# LB_BIT_i25_mp3Player-v03_3_3_OHW.net
KiCad netlist of a schematic drawn in EAGLE
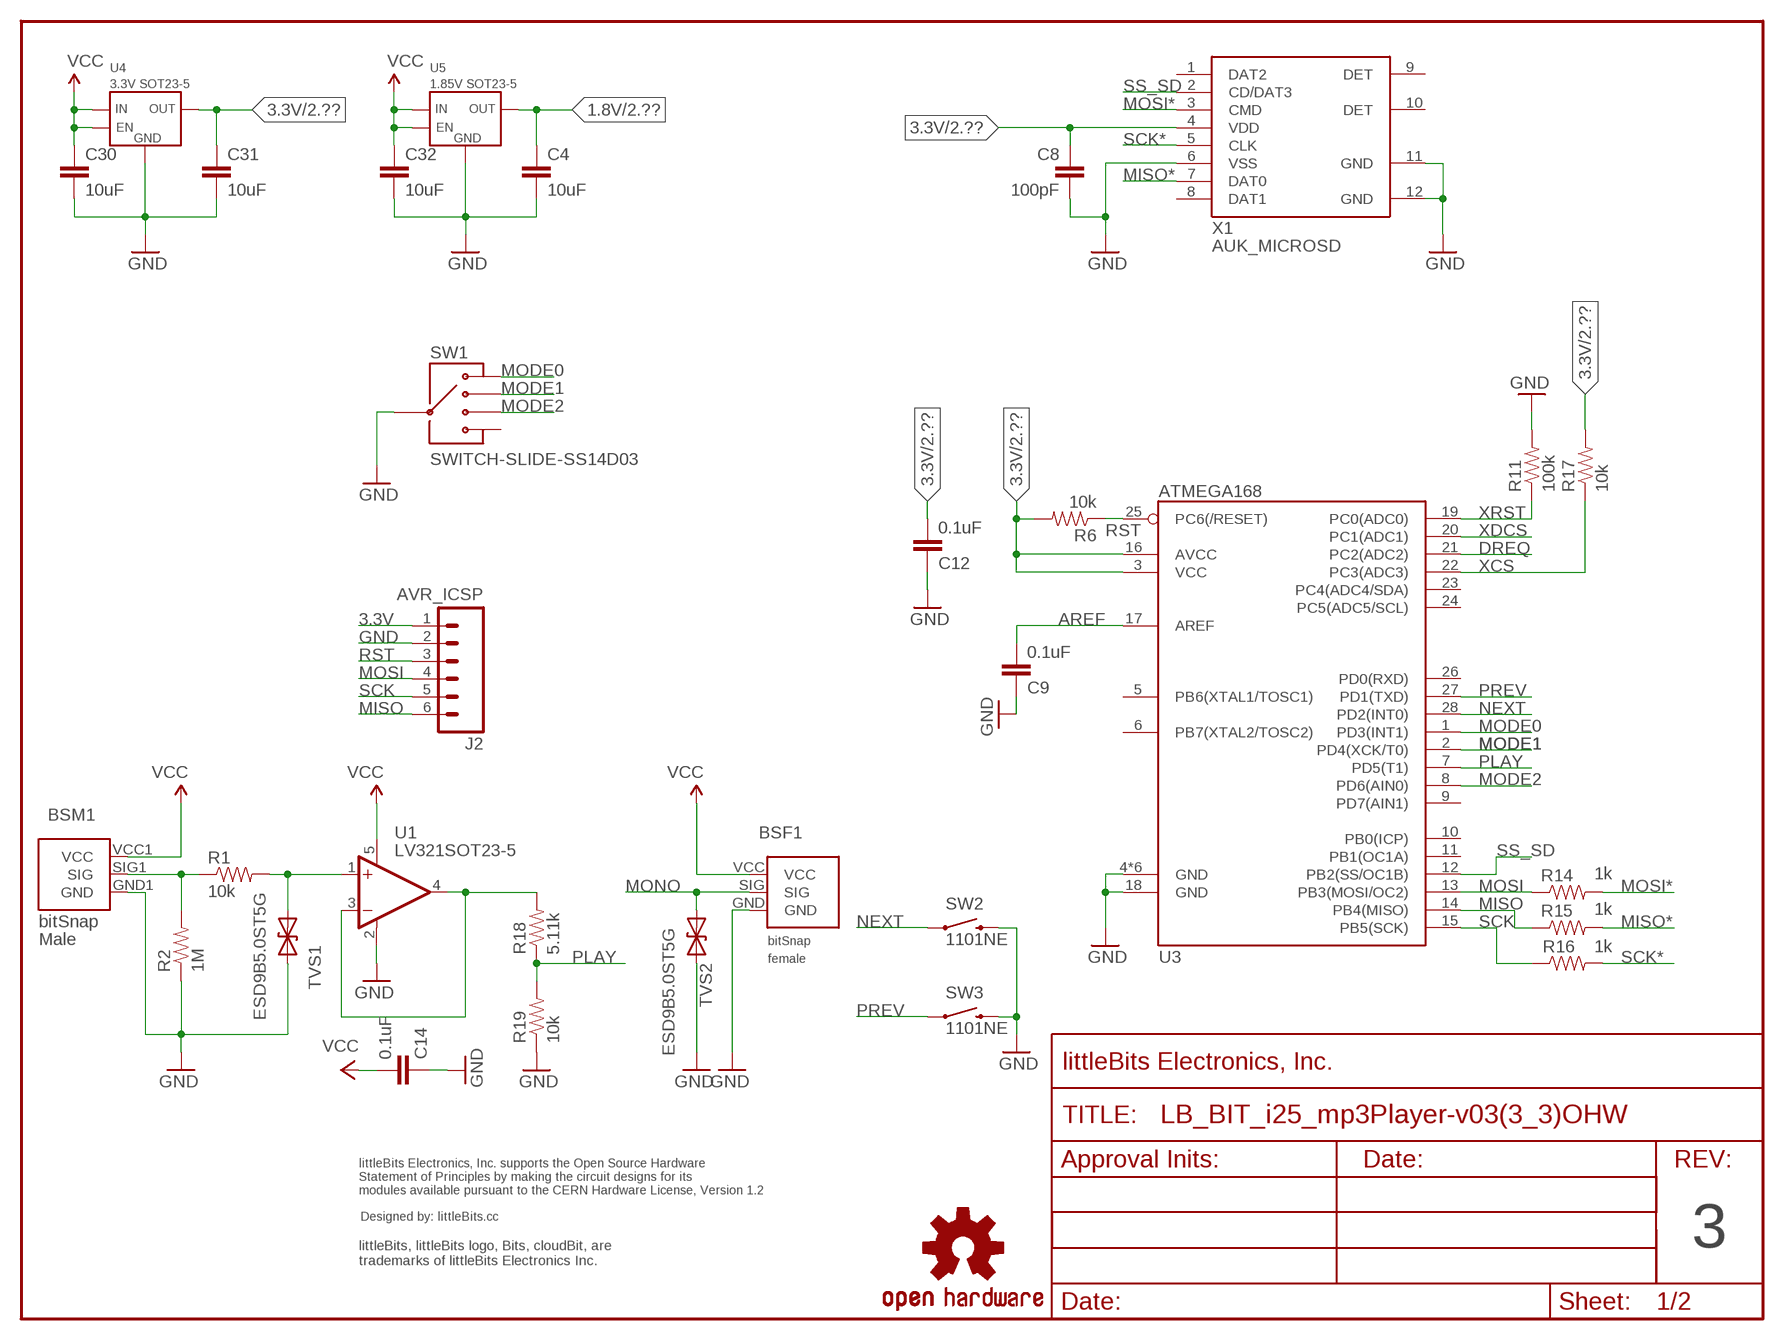
[diagram p0: schematic, sheet 1]
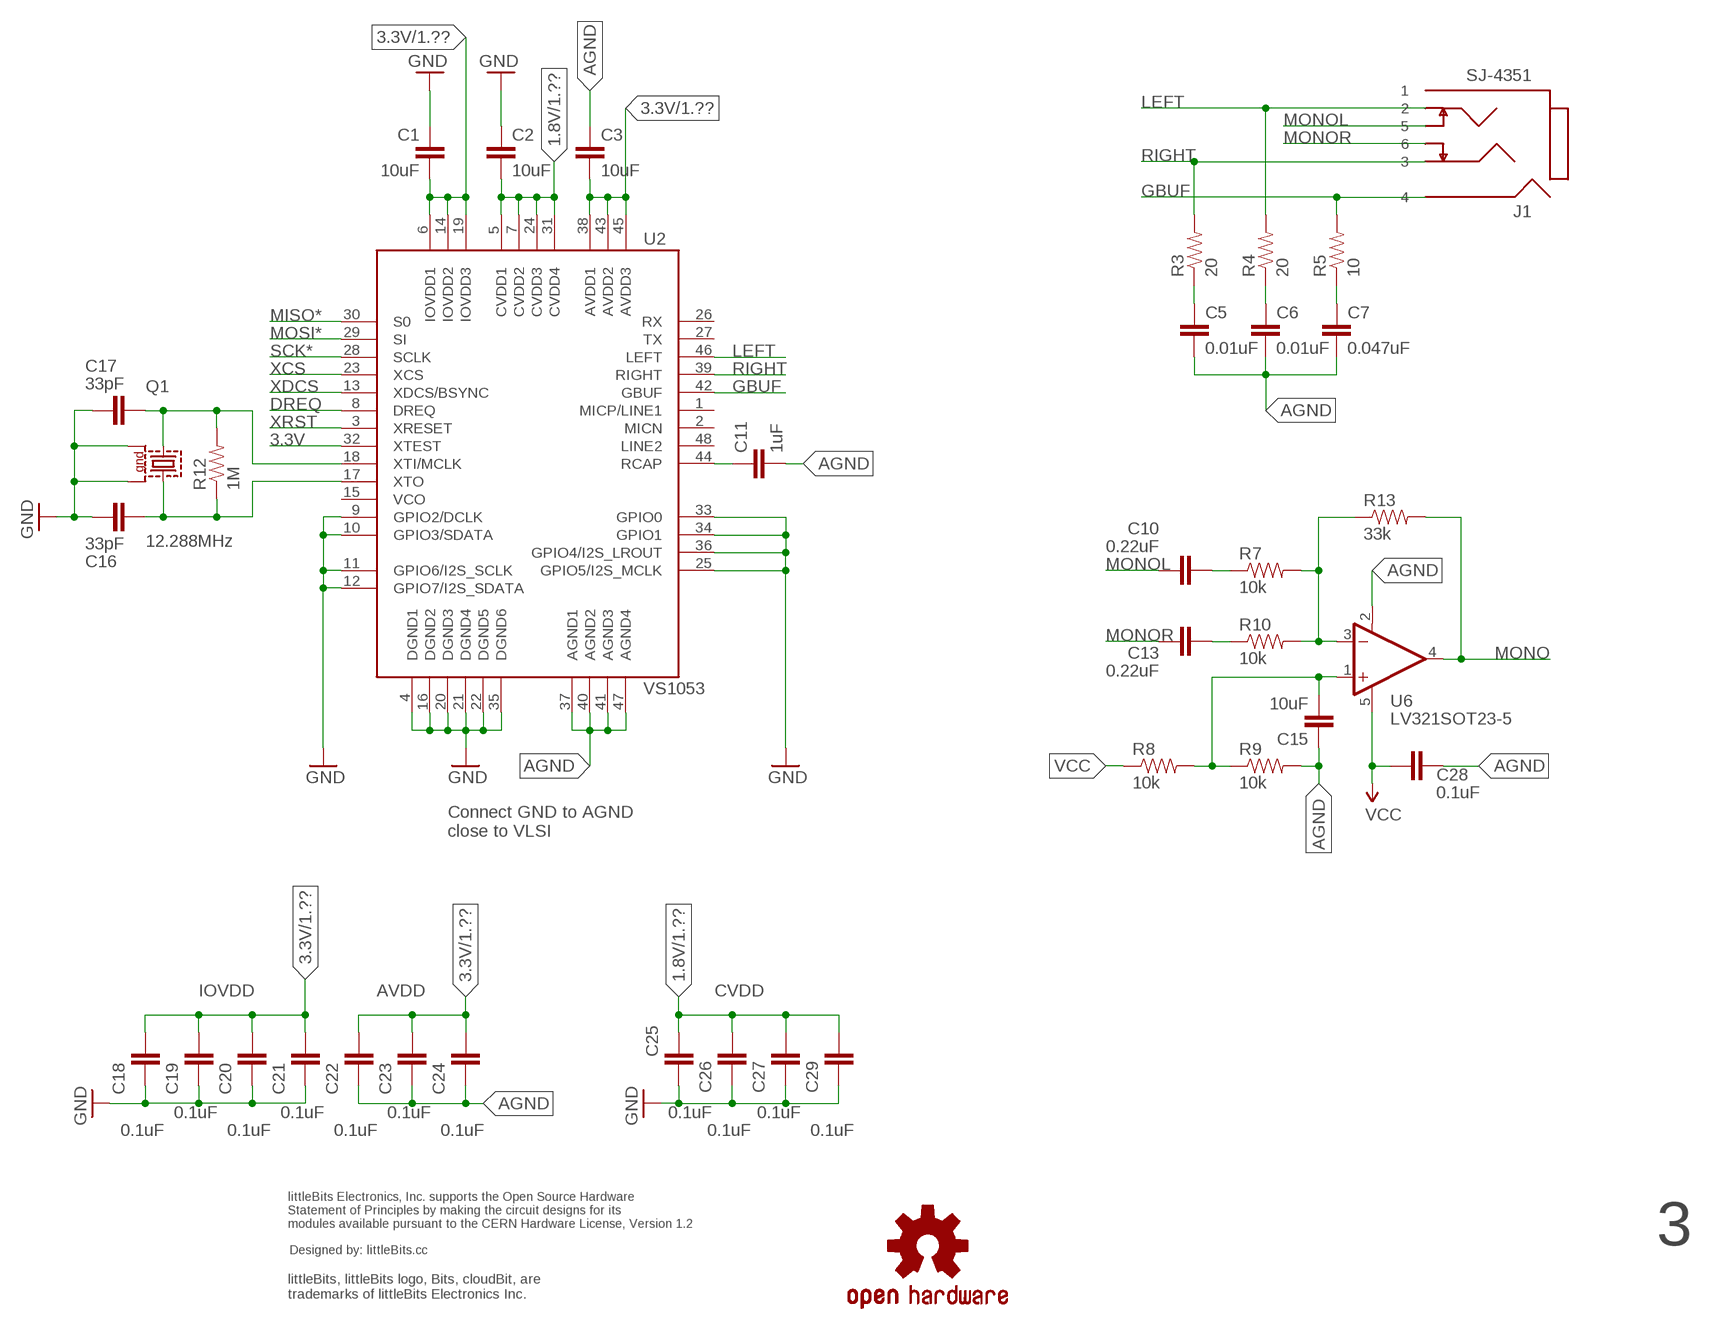
[diagram p1: schematic, sheet 2]

(export (version "E")
  (design (tool "Eeschema 10.0.6"))
  (components
    (comp (ref "BSF1")
      (value "BITSNAP_V03_FEMALE")
      (footprint "eagle-import:BITSNAP_V03_FEMALE")
      (libsource (lib "eagle-import") (part "BITSNAP_V03_FEMALE"))
    )
    (comp (ref "BSM1")
      (value "BITSNAP_V03_MALE")
      (footprint "eagle-import:BITSNAP_V03_MALE")
      (libsource (lib "eagle-import") (part "BITSNAP_V03_MALE"))
    )
    (comp (ref "C4")
      (value "10uF")
      (footprint "eagle-import:CAP-0603")
      (libsource (lib "eagle-import") (part "CAPCAP-0603"))
    )
    (comp (ref "C8")
      (value "100pF")
      (footprint "eagle-import:CAP-0603")
      (libsource (lib "eagle-import") (part "CAPCAP-0603"))
    )
    (comp (ref "C9")
      (value "0.1uF")
      (footprint "eagle-import:CAP-0402")
      (libsource (lib "eagle-import") (part "CAPCAP-0402"))
    )
    (comp (ref "C12")
      (value "0.1uF")
      (footprint "eagle-import:CAP-0402")
      (libsource (lib "eagle-import") (part "CAPCAP-0402"))
    )
    (comp (ref "C14")
      (value "0.1uF")
      (footprint "eagle-import:CAP-0603")
      (libsource (lib "eagle-import") (part "CAPCAP-0603"))
    )
    (comp (ref "C30")
      (value "10uF")
      (footprint "eagle-import:CAP-0603")
      (libsource (lib "eagle-import") (part "CAPCAP-0603"))
    )
    (comp (ref "C31")
      (value "10uF")
      (footprint "eagle-import:CAP-0603")
      (libsource (lib "eagle-import") (part "CAPCAP-0603"))
    )
    (comp (ref "C32")
      (value "10uF")
      (footprint "eagle-import:CAP-0603")
      (libsource (lib "eagle-import") (part "CAPCAP-0603"))
    )
    (comp (ref "J2")
      (value "AVR_ICSP")
      (footprint "eagle-import:SIP6-SM-0.1IN-NOS.S-MIN")
      (libsource (lib "eagle-import") (part "HRD-60.1INCH_NO_SILKSCREEN_SMALL"))
    )
    (comp (ref "R1")
      (value "10k")
      (footprint "eagle-import:RES-0603")
      (libsource (lib "eagle-import") (part "RESISTOR0603"))
    )
    (comp (ref "R2")
      (value "1M")
      (footprint "eagle-import:RES-0603")
      (libsource (lib "eagle-import") (part "RESISTOR0603"))
    )
    (comp (ref "R6")
      (value "10k")
      (footprint "eagle-import:RES-0603")
      (libsource (lib "eagle-import") (part "RESISTOR0603"))
    )
    (comp (ref "R11")
      (value "100k")
      (footprint "eagle-import:RES-0603")
      (libsource (lib "eagle-import") (part "RESISTOR0603"))
    )
    (comp (ref "R14")
      (value "1k")
      (footprint "eagle-import:RES-0603")
      (libsource (lib "eagle-import") (part "RESISTOR0603"))
    )
    (comp (ref "R15")
      (value "1k")
      (footprint "eagle-import:RES-0603")
      (libsource (lib "eagle-import") (part "RESISTOR0603"))
    )
    (comp (ref "R16")
      (value "1k")
      (footprint "eagle-import:RES-0603")
      (libsource (lib "eagle-import") (part "RESISTOR0603"))
    )
    (comp (ref "R17")
      (value "10k")
      (footprint "eagle-import:RES-0603")
      (libsource (lib "eagle-import") (part "RESISTOR0603"))
    )
    (comp (ref "R18")
      (value "5.11k")
      (footprint "eagle-import:RES-0603")
      (libsource (lib "eagle-import") (part "RESISTOR0603"))
    )
    (comp (ref "R19")
      (value "10k")
      (footprint "eagle-import:RES-0603")
      (libsource (lib "eagle-import") (part "RESISTOR0603"))
    )
    (comp (ref "SW1")
      (value "SWITCH-SLIDE-SS14D03")
      (footprint "eagle-import:SWITCH-SLIDE-SP4T-SS14D03")
      (fields (field (name "MFG") "Vimex") (field (name "MPN") "SS-14D03"))
      (libsource (lib "eagle-import") (part "SWITCH-SLIDE-SS14D03"))
    )
    (comp (ref "SW2")
      (value "1101NE")
      (footprint "eagle-import:TACTILE-SWITCH-1101NE")
      (libsource (lib "eagle-import") (part "SWITCH-MOMENTARY-2-SMD-1101NE"))
    )
    (comp (ref "SW3")
      (value "1101NE")
      (footprint "eagle-import:TACTILE-SWITCH-1101NE")
      (libsource (lib "eagle-import") (part "SWITCH-MOMENTARY-2-SMD-1101NE"))
    )
    (comp (ref "TVS1")
      (value "ESD9B5.0ST5G")
      (footprint "eagle-import:SOD-923")
      (libsource (lib "eagle-import") (part "DIODE-TVSSOD-923"))
    )
    (comp (ref "TVS2")
      (value "ESD9B5.0ST5G")
      (footprint "eagle-import:SOD-923")
      (libsource (lib "eagle-import") (part "DIODE-TVSSOD-923"))
    )
    (comp (ref "U$1")
      (value "OSHWCREDIT")
      (footprint "eagle-import:OSHWCREDIT")
      (libsource (lib "eagle-import") (part "OSHWCREDIT"))
    )
    (comp (ref "U$2")
      (value "OSHW-LOGOL")
      (footprint "eagle-import:OSHW-LOGO-L")
      (libsource (lib "eagle-import") (part "OSHW-LOGOL"))
    )
    (comp (ref "U$38")
      (value "FRAME-LETTER-OHWOHW")
      (footprint "eagle-import:FABDWG01-OHW")
      (libsource (lib "eagle-import") (part "FRAME-LETTER-OHWOHW"))
    )
    (comp (ref "U1")
      (value "LV321SOT23-5")
      (footprint "eagle-import:SOT23-5")
      (libsource (lib "eagle-import") (part "LV321SOT23-5"))
    )
    (comp (ref "U3")
      (value "ATMEGA168")
      (footprint "eagle-import:VQFN28")
      (libsource (lib "eagle-import") (part "ATMEGA168-28PINVFQFN-28"))
    )
    (comp (ref "U4")
      (value "3.3V SOT23-5")
      (footprint "eagle-import:SOT23-5")
      (libsource (lib "eagle-import") (part "V_REG_SOT23-5_EN"))
    )
    (comp (ref "U5")
      (value "1.85V SOT23-5")
      (footprint "eagle-import:SOT23-5")
      (libsource (lib "eagle-import") (part "V_REG_SOT23-5_EN"))
    )
    (comp (ref "X1")
      (value "AUK_MICROSD")
      (footprint "eagle-import:AUK_TFC08WP01-R1K-H")
      (libsource (lib "eagle-import") (part "AUK_MICROSD"))
    )
    (comp (ref "C1")
      (value "10uF")
      (footprint "eagle-import:CAP-0603")
      (libsource (lib "eagle-import") (part "CAPCAP-0603"))
    )
    (comp (ref "C2")
      (value "10uF")
      (footprint "eagle-import:CAP-0603")
      (libsource (lib "eagle-import") (part "CAPCAP-0603"))
    )
    (comp (ref "C3")
      (value "10uF")
      (footprint "eagle-import:CAP-0603")
      (libsource (lib "eagle-import") (part "CAPCAP-0603"))
    )
    (comp (ref "C5")
      (value "0.01uF")
      (footprint "eagle-import:CAP-0603")
      (libsource (lib "eagle-import") (part "CAPCAP-0603"))
    )
    (comp (ref "C6")
      (value "0.01uF")
      (footprint "eagle-import:CAP-0603")
      (libsource (lib "eagle-import") (part "CAPCAP-0603"))
    )
    (comp (ref "C7")
      (value "0.047uF")
      (footprint "eagle-import:CAP-0603")
      (libsource (lib "eagle-import") (part "CAPCAP-0603"))
    )
    (comp (ref "C10")
      (value "0.22uF")
      (footprint "eagle-import:CAP-0603")
      (libsource (lib "eagle-import") (part "CAPCAP-0603"))
    )
    (comp (ref "C11")
      (value "1uF")
      (footprint "eagle-import:CAP-0402")
      (libsource (lib "eagle-import") (part "CAPCAP-0402"))
    )
    (comp (ref "C13")
      (value "0.22uF")
      (footprint "eagle-import:CAP-0603")
      (libsource (lib "eagle-import") (part "CAPCAP-0603"))
    )
    (comp (ref "C15")
      (value "10uF")
      (footprint "eagle-import:CAP-0603")
      (libsource (lib "eagle-import") (part "CAPCAP-0603"))
    )
    (comp (ref "C16")
      (value "33pF")
      (footprint "eagle-import:CAP-0603")
      (libsource (lib "eagle-import") (part "CAPCAP-0603"))
    )
    (comp (ref "C17")
      (value "33pF")
      (footprint "eagle-import:CAP-0603")
      (libsource (lib "eagle-import") (part "CAPCAP-0603"))
    )
    (comp (ref "C18")
      (value "0.1uF")
      (footprint "eagle-import:CAP-0402")
      (libsource (lib "eagle-import") (part "CAPCAP-0402"))
    )
    (comp (ref "C19")
      (value "0.1uF")
      (footprint "eagle-import:CAP-0402")
      (libsource (lib "eagle-import") (part "CAPCAP-0402"))
    )
    (comp (ref "C20")
      (value "0.1uF")
      (footprint "eagle-import:CAP-0402")
      (libsource (lib "eagle-import") (part "CAPCAP-0402"))
    )
    (comp (ref "C21")
      (value "0.1uF")
      (footprint "eagle-import:CAP-0402")
      (libsource (lib "eagle-import") (part "CAPCAP-0402"))
    )
    (comp (ref "C22")
      (value "0.1uF")
      (footprint "eagle-import:CAP-0402")
      (libsource (lib "eagle-import") (part "CAPCAP-0402"))
    )
    (comp (ref "C23")
      (value "0.1uF")
      (footprint "eagle-import:CAP-0402")
      (libsource (lib "eagle-import") (part "CAPCAP-0402"))
    )
    (comp (ref "C24")
      (value "0.1uF")
      (footprint "eagle-import:CAP-0402")
      (libsource (lib "eagle-import") (part "CAPCAP-0402"))
    )
    (comp (ref "C25")
      (value "0.1uF")
      (footprint "eagle-import:CAP-0402")
      (libsource (lib "eagle-import") (part "CAPCAP-0402"))
    )
    (comp (ref "C26")
      (value "0.1uF")
      (footprint "eagle-import:CAP-0402")
      (libsource (lib "eagle-import") (part "CAPCAP-0402"))
    )
    (comp (ref "C27")
      (value "0.1uF")
      (footprint "eagle-import:CAP-0402")
      (libsource (lib "eagle-import") (part "CAPCAP-0402"))
    )
    (comp (ref "C28")
      (value "0.1uF")
      (footprint "eagle-import:CAP-0603")
      (libsource (lib "eagle-import") (part "CAPCAP-0603"))
    )
    (comp (ref "C29")
      (value "0.1uF")
      (footprint "eagle-import:CAP-0402")
      (libsource (lib "eagle-import") (part "CAPCAP-0402"))
    )
    (comp (ref "J1")
      (value "SJ-4351")
      (footprint "eagle-import:CUI-SJ-4351")
      (libsource (lib "eagle-import") (part "JACK-PHONO-4COND-SW"))
    )
    (comp (ref "Q1")
      (value "12.288MHz")
      (footprint "eagle-import:CRYSTAL-SMD-7B-SERIES-5X3.2MM")
      (fields (field (name "MFG") "TXC") (field (name "MPN") "7B SERIES"))
      (libsource (lib "eagle-import") (part "CRYSTAL-SMD-7B-SERIES-TXC"))
    )
    (comp (ref "R3")
      (value "20")
      (footprint "eagle-import:RES-0603")
      (libsource (lib "eagle-import") (part "RESISTOR0603"))
    )
    (comp (ref "R4")
      (value "20")
      (footprint "eagle-import:RES-0603")
      (libsource (lib "eagle-import") (part "RESISTOR0603"))
    )
    (comp (ref "R5")
      (value "10")
      (footprint "eagle-import:RES-0603")
      (libsource (lib "eagle-import") (part "RESISTOR0603"))
    )
    (comp (ref "R7")
      (value "10k")
      (footprint "eagle-import:RES-0603")
      (libsource (lib "eagle-import") (part "RESISTOR0603"))
    )
    (comp (ref "R8")
      (value "10k")
      (footprint "eagle-import:RES-0603")
      (libsource (lib "eagle-import") (part "RESISTOR0603"))
    )
    (comp (ref "R9")
      (value "10k")
      (footprint "eagle-import:RES-0603")
      (libsource (lib "eagle-import") (part "RESISTOR0603"))
    )
    (comp (ref "R10")
      (value "10k")
      (footprint "eagle-import:RES-0603")
      (libsource (lib "eagle-import") (part "RESISTOR0603"))
    )
    (comp (ref "R12")
      (value "1M")
      (footprint "eagle-import:RES-0603")
      (libsource (lib "eagle-import") (part "RESISTOR0603"))
    )
    (comp (ref "R13")
      (value "33k")
      (footprint "eagle-import:RES-0603")
      (libsource (lib "eagle-import") (part "RESISTOR0603"))
    )
    (comp (ref "U$32")
      (value "OSHWCREDIT")
      (footprint "eagle-import:OSHWCREDIT")
      (libsource (lib "eagle-import") (part "OSHWCREDIT"))
    )
    (comp (ref "U$33")
      (value "OSHW-LOGOL")
      (footprint "eagle-import:OSHW-LOGO-L")
      (libsource (lib "eagle-import") (part "OSHW-LOGOL"))
    )
    (comp (ref "U2")
      (value "VS1053")
      (footprint "eagle-import:LQFP-48")
      (libsource (lib "eagle-import") (part "VS1053"))
    )
    (comp (ref "U6")
      (value "LV321SOT23-5")
      (footprint "eagle-import:SOT23-5")
      (libsource (lib "eagle-import") (part "LV321SOT23-5"))
    )
  )
  (nets
    (net (code "1") (name "1.8V") (class "Default")
      (node (ref "C2") (pin "2") (pinfunction "2_2") (pintype "passive"))
      (node (ref "C25") (pin "1") (pinfunction "1_1") (pintype "passive"))
      (node (ref "C26") (pin "1") (pinfunction "1_1") (pintype "passive"))
      (node (ref "C27") (pin "1") (pinfunction "1_1") (pintype "passive"))
      (node (ref "C29") (pin "1") (pinfunction "1_1") (pintype "passive"))
      (node (ref "C4") (pin "1") (pinfunction "1_1") (pintype "passive"))
      (node (ref "U2") (pin "24") (pinfunction "CVDD3_24") (pintype "bidirectional"))
      (node (ref "U2") (pin "31") (pinfunction "CVDD4_31") (pintype "bidirectional"))
      (node (ref "U2") (pin "5") (pinfunction "CVDD1_5") (pintype "bidirectional"))
      (node (ref "U2") (pin "7") (pinfunction "CVDD2_7") (pintype "bidirectional"))
      (node (ref "U5") (pin "5") (pinfunction "OUT_5") (pintype "passive"))
    )
    (net (code "2") (name "3.3V") (class "Default")
      (node (ref "C1") (pin "2") (pinfunction "2_2") (pintype "passive"))
      (node (ref "C12") (pin "2") (pinfunction "2_2") (pintype "passive"))
      (node (ref "C18") (pin "1") (pinfunction "1_1") (pintype "passive"))
      (node (ref "C19") (pin "1") (pinfunction "1_1") (pintype "passive"))
      (node (ref "C20") (pin "1") (pinfunction "1_1") (pintype "passive"))
      (node (ref "C21") (pin "1") (pinfunction "1_1") (pintype "passive"))
      (node (ref "C22") (pin "1") (pinfunction "1_1") (pintype "passive"))
      (node (ref "C23") (pin "1") (pinfunction "1_1") (pintype "passive"))
      (node (ref "C24") (pin "1") (pinfunction "1_1") (pintype "passive"))
      (node (ref "C3") (pin "2") (pinfunction "2_2") (pintype "passive"))
      (node (ref "C31") (pin "1") (pinfunction "1_1") (pintype "passive"))
      (node (ref "C8") (pin "1") (pinfunction "1_1") (pintype "passive"))
      (node (ref "J2") (pin "1") (pinfunction "1_1") (pintype "passive"))
      (node (ref "R17") (pin "2") (pinfunction "2_2") (pintype "passive"))
      (node (ref "R6") (pin "2") (pinfunction "2_2") (pintype "passive"))
      (node (ref "U2") (pin "14") (pinfunction "IOVDD2_14") (pintype "bidirectional"))
      (node (ref "U2") (pin "19") (pinfunction "IOVDD3_19") (pintype "bidirectional"))
      (node (ref "U2") (pin "32") (pinfunction "XTEST_32") (pintype "bidirectional"))
      (node (ref "U2") (pin "38") (pinfunction "AVDD1_38") (pintype "bidirectional"))
      (node (ref "U2") (pin "43") (pinfunction "AVDD2_43") (pintype "bidirectional"))
      (node (ref "U2") (pin "45") (pinfunction "AVDD3_45") (pintype "bidirectional"))
      (node (ref "U2") (pin "6") (pinfunction "IOVDD1_6") (pintype "bidirectional"))
      (node (ref "U3") (pin "16") (pinfunction "AVCC_16") (pintype "bidirectional"))
      (node (ref "U3") (pin "3") (pinfunction "VCC_3") (pintype "bidirectional"))
      (node (ref "U4") (pin "5") (pinfunction "OUT_5") (pintype "passive"))
      (node (ref "X1") (pin "4") (pinfunction "VDD_4") (pintype "bidirectional"))
    )
    (net (code "3") (name "AGND") (class "Default")
      (node (ref "C11") (pin "2") (pinfunction "2_2") (pintype "passive"))
      (node (ref "C15") (pin "1") (pinfunction "1_1") (pintype "passive"))
      (node (ref "C22") (pin "2") (pinfunction "2_2") (pintype "passive"))
      (node (ref "C23") (pin "2") (pinfunction "2_2") (pintype "passive"))
      (node (ref "C24") (pin "2") (pinfunction "2_2") (pintype "passive"))
      (node (ref "C28") (pin "1") (pinfunction "1_1") (pintype "passive"))
      (node (ref "C3") (pin "1") (pinfunction "1_1") (pintype "passive"))
      (node (ref "C5") (pin "2") (pinfunction "2_2") (pintype "passive"))
      (node (ref "C6") (pin "2") (pinfunction "2_2") (pintype "passive"))
      (node (ref "C7") (pin "2") (pinfunction "2_2") (pintype "passive"))
      (node (ref "R9") (pin "2") (pinfunction "2_2") (pintype "passive"))
      (node (ref "U2") (pin "37") (pinfunction "AGND1_37") (pintype "bidirectional"))
      (node (ref "U2") (pin "40") (pinfunction "AGND2_40") (pintype "bidirectional"))
      (node (ref "U2") (pin "41") (pinfunction "AGND3_41") (pintype "bidirectional"))
      (node (ref "U2") (pin "47") (pinfunction "AGND4_47") (pintype "bidirectional"))
      (node (ref "U6") (pin "2") (pinfunction "V-_2") (pintype "power_in"))
    )
    (net (code "4") (name "AREF") (class "Default")
      (node (ref "C9") (pin "2") (pinfunction "2_2") (pintype "passive"))
      (node (ref "U3") (pin "17") (pinfunction "AREF_17") (pintype "bidirectional"))
    )
    (net (code "5") (name "DREQ") (class "Default")
      (node (ref "U2") (pin "8") (pinfunction "DREQ_8") (pintype "bidirectional"))
      (node (ref "U3") (pin "21") (pinfunction "PC2(ADC2)_21") (pintype "bidirectional"))
    )
    (net (code "6") (name "GBUF") (class "Default")
      (node (ref "J1") (pin "4") (pinfunction "4_4") (pintype "bidirectional"))
      (node (ref "R5") (pin "2") (pinfunction "2_2") (pintype "passive"))
      (node (ref "U2") (pin "42") (pinfunction "GBUF_42") (pintype "bidirectional"))
    )
    (net (code "7") (name "GND") (class "Default")
      (node (ref "BSF1") (pin "GND") (pinfunction "GND_GND") (pintype "bidirectional"))
      (node (ref "BSM1") (pin "GND1") (pinfunction "GND_GND1") (pintype "bidirectional"))
      (node (ref "C1") (pin "1") (pinfunction "1_1") (pintype "passive"))
      (node (ref "C12") (pin "1") (pinfunction "1_1") (pintype "passive"))
      (node (ref "C14") (pin "1") (pinfunction "1_1") (pintype "passive"))
      (node (ref "C16") (pin "2") (pinfunction "2_2") (pintype "passive"))
      (node (ref "C17") (pin "2") (pinfunction "2_2") (pintype "passive"))
      (node (ref "C18") (pin "2") (pinfunction "2_2") (pintype "passive"))
      (node (ref "C19") (pin "2") (pinfunction "2_2") (pintype "passive"))
      (node (ref "C2") (pin "1") (pinfunction "1_1") (pintype "passive"))
      (node (ref "C20") (pin "2") (pinfunction "2_2") (pintype "passive"))
      (node (ref "C21") (pin "2") (pinfunction "2_2") (pintype "passive"))
      (node (ref "C25") (pin "2") (pinfunction "2_2") (pintype "passive"))
      (node (ref "C26") (pin "2") (pinfunction "2_2") (pintype "passive"))
      (node (ref "C27") (pin "2") (pinfunction "2_2") (pintype "passive"))
      (node (ref "C29") (pin "2") (pinfunction "2_2") (pintype "passive"))
      (node (ref "C30") (pin "2") (pinfunction "2_2") (pintype "passive"))
      (node (ref "C31") (pin "2") (pinfunction "2_2") (pintype "passive"))
      (node (ref "C32") (pin "2") (pinfunction "2_2") (pintype "passive"))
      (node (ref "C4") (pin "2") (pinfunction "2_2") (pintype "passive"))
      (node (ref "C8") (pin "2") (pinfunction "2_2") (pintype "passive"))
      (node (ref "C9") (pin "1") (pinfunction "1_1") (pintype "passive"))
      (node (ref "J2") (pin "2") (pinfunction "2_2") (pintype "passive"))
      (node (ref "Q1") (pin "P$2") (pinfunction "2_P$2") (pintype "passive"))
      (node (ref "Q1") (pin "P$4") (pinfunction "4_P$4") (pintype "passive"))
      (node (ref "R11") (pin "2") (pinfunction "2_2") (pintype "passive"))
      (node (ref "R19") (pin "1") (pinfunction "1_1") (pintype "passive"))
      (node (ref "R2") (pin "1") (pinfunction "1_1") (pintype "passive"))
      (node (ref "SW1") (pin "COM") (pinfunction "COM_COM") (pintype "bidirectional"))
      (node (ref "SW2") (pin "P$2") (pinfunction "2_P$2") (pintype "passive"))
      (node (ref "SW3") (pin "P$2") (pinfunction "2_P$2") (pintype "passive"))
      (node (ref "TVS1") (pin "2") (pinfunction "C_2") (pintype "passive"))
      (node (ref "TVS2") (pin "2") (pinfunction "C_2") (pintype "passive"))
      (node (ref "U1") (pin "2") (pinfunction "V-_2") (pintype "power_in"))
      (node (ref "U2") (pin "10") (pinfunction "GPIO3/SDATA_10") (pintype "bidirectional"))
      (node (ref "U2") (pin "11") (pinfunction "GPIO6/I2S_SCLK_11") (pintype "bidirectional"))
      (node (ref "U2") (pin "12") (pinfunction "GPIO7/I2S_SDATA_12") (pintype "bidirectional"))
      (node (ref "U2") (pin "16") (pinfunction "DGND2_16") (pintype "bidirectional"))
      (node (ref "U2") (pin "20") (pinfunction "DGND3_20") (pintype "bidirectional"))
      (node (ref "U2") (pin "21") (pinfunction "DGND4_21") (pintype "bidirectional"))
      (node (ref "U2") (pin "22") (pinfunction "DGND5_22") (pintype "bidirectional"))
      (node (ref "U2") (pin "25") (pinfunction "GPIO5/I2S_MCLK_25") (pintype "bidirectional"))
      (node (ref "U2") (pin "33") (pinfunction "GPIO0_33") (pintype "bidirectional"))
      (node (ref "U2") (pin "34") (pinfunction "GPIO1_34") (pintype "bidirectional"))
      (node (ref "U2") (pin "35") (pinfunction "DGND6_35") (pintype "bidirectional"))
      (node (ref "U2") (pin "36") (pinfunction "GPIO4/I2S_LROUT_36") (pintype "bidirectional"))
      (node (ref "U2") (pin "4") (pinfunction "DGND1_4") (pintype "bidirectional"))
      (node (ref "U2") (pin "9") (pinfunction "GPIO2/DCLK_9") (pintype "bidirectional"))
      (node (ref "U3") (pin "18") (pinfunction "GND_18") (pintype "bidirectional"))
      (node (ref "U3") (pin "4") (pinfunction "GND_4") (pintype "bidirectional"))
      (node (ref "U3") (pin "TH") (pinfunction "GND_TH") (pintype "bidirectional"))
      (node (ref "U3") (pin "TH@1") (pinfunction "GND_TH@1") (pintype "bidirectional"))
      (node (ref "U3") (pin "TH@2") (pinfunction "GND_TH@2") (pintype "bidirectional"))
      (node (ref "U3") (pin "TH@3") (pinfunction "GND_TH@3") (pintype "bidirectional"))
      (node (ref "U3") (pin "TH@4") (pinfunction "GND_TH@4") (pintype "bidirectional"))
      (node (ref "U4") (pin "2") (pinfunction "GND_2") (pintype "input"))
      (node (ref "U5") (pin "2") (pinfunction "GND_2") (pintype "input"))
      (node (ref "X1") (pin "11") (pinfunction "GND_11") (pintype "bidirectional"))
      (node (ref "X1") (pin "12") (pinfunction "GND_12") (pintype "bidirectional"))
      (node (ref "X1") (pin "6") (pinfunction "VSS_6") (pintype "bidirectional"))
    )
    (net (code "8") (name "LEFT") (class "Default")
      (node (ref "J1") (pin "2") (pinfunction "2_2") (pintype "bidirectional"))
      (node (ref "R4") (pin "2") (pinfunction "2_2") (pintype "passive"))
      (node (ref "U2") (pin "46") (pinfunction "LEFT_46") (pintype "bidirectional"))
    )
    (net (code "9") (name "MISO") (class "Default")
      (node (ref "J2") (pin "6") (pinfunction "6_6") (pintype "passive"))
      (node (ref "R15") (pin "1") (pinfunction "1_1") (pintype "passive"))
      (node (ref "U3") (pin "14") (pinfunction "PB4(MISO)_14") (pintype "bidirectional"))
    )
    (net (code "10") (name "MISO*") (class "Default")
      (node (ref "R15") (pin "2") (pinfunction "2_2") (pintype "passive"))
      (node (ref "U2") (pin "30") (pinfunction "S0_30") (pintype "bidirectional"))
      (node (ref "X1") (pin "7") (pinfunction "DAT0_7") (pintype "bidirectional"))
    )
    (net (code "11") (name "MODE0") (class "Default")
      (node (ref "SW1") (pin "1") (pinfunction "1_1") (pintype "bidirectional"))
      (node (ref "U3") (pin "1") (pinfunction "PD3(INT1)_1") (pintype "bidirectional"))
    )
    (net (code "12") (name "MODE1") (class "Default")
      (node (ref "SW1") (pin "2") (pinfunction "2_2") (pintype "bidirectional"))
      (node (ref "U3") (pin "2") (pinfunction "PD4(XCK/T0)_2") (pintype "bidirectional"))
    )
    (net (code "13") (name "MODE2") (class "Default")
      (node (ref "SW1") (pin "3") (pinfunction "3_3") (pintype "bidirectional"))
      (node (ref "U3") (pin "8") (pinfunction "PD6(AIN0)_8") (pintype "bidirectional"))
    )
    (net (code "14") (name "MONO") (class "Default")
      (node (ref "BSF1") (pin "SIG") (pinfunction "SIG_SIG") (pintype "bidirectional"))
      (node (ref "R13") (pin "2") (pinfunction "2_2") (pintype "passive"))
      (node (ref "TVS2") (pin "1") (pinfunction "A_1") (pintype "passive"))
      (node (ref "U6") (pin "4") (pinfunction "OUT_4") (pintype "output"))
    )
    (net (code "15") (name "MONOL") (class "Default")
      (node (ref "C10") (pin "2") (pinfunction "2_2") (pintype "passive"))
      (node (ref "J1") (pin "5") (pinfunction "5_5") (pintype "bidirectional"))
    )
    (net (code "16") (name "MONOR") (class "Default")
      (node (ref "C13") (pin "2") (pinfunction "2_2") (pintype "passive"))
      (node (ref "J1") (pin "6") (pinfunction "6_6") (pintype "bidirectional"))
    )
    (net (code "17") (name "MOSI") (class "Default")
      (node (ref "J2") (pin "4") (pinfunction "4_4") (pintype "passive"))
      (node (ref "R14") (pin "1") (pinfunction "1_1") (pintype "passive"))
      (node (ref "U3") (pin "13") (pinfunction "PB3(MOSI/OC2)_13") (pintype "bidirectional"))
    )
    (net (code "18") (name "MOSI*") (class "Default")
      (node (ref "R14") (pin "2") (pinfunction "2_2") (pintype "passive"))
      (node (ref "U2") (pin "29") (pinfunction "SI_29") (pintype "bidirectional"))
      (node (ref "X1") (pin "3") (pinfunction "CMD_3") (pintype "bidirectional"))
    )
    (net (code "19") (name "NEXT") (class "Default")
      (node (ref "SW2") (pin "P$1") (pinfunction "1_P$1") (pintype "passive"))
      (node (ref "U3") (pin "28") (pinfunction "PD2(INT0)_28") (pintype "bidirectional"))
    )
    (net (code "20") (name "Net-(BSM1-SIG)") (class "Default")
      (node (ref "BSM1") (pin "SIG1") (pinfunction "SIG_SIG1") (pintype "bidirectional"))
      (node (ref "R1") (pin "1") (pinfunction "1_1") (pintype "passive"))
      (node (ref "R2") (pin "2") (pinfunction "2_2") (pintype "passive"))
    )
    (net (code "21") (name "Net-(C5-Pad1)") (class "Default")
      (node (ref "C5") (pin "1") (pinfunction "1_1") (pintype "passive"))
      (node (ref "R3") (pin "1") (pinfunction "1_1") (pintype "passive"))
    )
    (net (code "22") (name "Net-(C6-Pad1)") (class "Default")
      (node (ref "C6") (pin "1") (pinfunction "1_1") (pintype "passive"))
      (node (ref "R4") (pin "1") (pinfunction "1_1") (pintype "passive"))
    )
    (net (code "23") (name "Net-(C7-Pad1)") (class "Default")
      (node (ref "C7") (pin "1") (pinfunction "1_1") (pintype "passive"))
      (node (ref "R5") (pin "1") (pinfunction "1_1") (pintype "passive"))
    )
    (net (code "24") (name "Net-(C10-Pad1)") (class "Default")
      (node (ref "C10") (pin "1") (pinfunction "1_1") (pintype "passive"))
      (node (ref "R7") (pin "1") (pinfunction "1_1") (pintype "passive"))
    )
    (net (code "25") (name "Net-(C13-Pad1)") (class "Default")
      (node (ref "C13") (pin "1") (pinfunction "1_1") (pintype "passive"))
      (node (ref "R10") (pin "1") (pinfunction "1_1") (pintype "passive"))
    )
    (net (code "26") (name "Net-(Q1-1)") (class "Default")
      (node (ref "C17") (pin "1") (pinfunction "1_1") (pintype "passive"))
      (node (ref "Q1") (pin "P$1") (pinfunction "1_P$1") (pintype "passive"))
      (node (ref "R12") (pin "2") (pinfunction "2_2") (pintype "passive"))
      (node (ref "U2") (pin "18") (pinfunction "XTI/MCLK_18") (pintype "bidirectional"))
    )
    (net (code "27") (name "Net-(Q1-3)") (class "Default")
      (node (ref "C16") (pin "1") (pinfunction "1_1") (pintype "passive"))
      (node (ref "Q1") (pin "P$3") (pinfunction "3_P$3") (pintype "passive"))
      (node (ref "R12") (pin "1") (pinfunction "1_1") (pintype "passive"))
      (node (ref "U2") (pin "17") (pinfunction "XTO_17") (pintype "bidirectional"))
    )
    (net (code "28") (name "Net-(TVS1-A)") (class "Default")
      (node (ref "R1") (pin "2") (pinfunction "2_2") (pintype "passive"))
      (node (ref "TVS1") (pin "1") (pinfunction "A_1") (pintype "passive"))
      (node (ref "U1") (pin "1") (pinfunction "+IN_1") (pintype "input"))
    )
    (net (code "29") (name "Net-(U1--IN)") (class "Default")
      (node (ref "R18") (pin "2") (pinfunction "2_2") (pintype "passive"))
      (node (ref "U1") (pin "3") (pinfunction "-IN_3") (pintype "input"))
      (node (ref "U1") (pin "4") (pinfunction "OUT_4") (pintype "output"))
    )
    (net (code "30") (name "Net-(U2-RCAP)") (class "Default")
      (node (ref "C11") (pin "1") (pinfunction "1_1") (pintype "passive"))
      (node (ref "U2") (pin "44") (pinfunction "RCAP_44") (pintype "bidirectional"))
    )
    (net (code "31") (name "Net-(U6-+IN)") (class "Default")
      (node (ref "C15") (pin "2") (pinfunction "2_2") (pintype "passive"))
      (node (ref "R8") (pin "2") (pinfunction "2_2") (pintype "passive"))
      (node (ref "R9") (pin "1") (pinfunction "1_1") (pintype "passive"))
      (node (ref "U6") (pin "1") (pinfunction "+IN_1") (pintype "input"))
    )
    (net (code "32") (name "Net-(U6--IN)") (class "Default")
      (node (ref "R10") (pin "2") (pinfunction "2_2") (pintype "passive"))
      (node (ref "R13") (pin "1") (pinfunction "1_1") (pintype "passive"))
      (node (ref "R7") (pin "2") (pinfunction "2_2") (pintype "passive"))
      (node (ref "U6") (pin "3") (pinfunction "-IN_3") (pintype "input"))
    )
    (net (code "33") (name "PLAY") (class "Default")
      (node (ref "R18") (pin "1") (pinfunction "1_1") (pintype "passive"))
      (node (ref "R19") (pin "2") (pinfunction "2_2") (pintype "passive"))
      (node (ref "U3") (pin "7") (pinfunction "PD5(T1)_7") (pintype "bidirectional"))
    )
    (net (code "34") (name "PREV") (class "Default")
      (node (ref "SW3") (pin "P$1") (pinfunction "1_P$1") (pintype "passive"))
      (node (ref "U3") (pin "27") (pinfunction "PD1(TXD)_27") (pintype "bidirectional"))
    )
    (net (code "35") (name "RIGHT") (class "Default")
      (node (ref "J1") (pin "3") (pinfunction "3_3") (pintype "bidirectional"))
      (node (ref "R3") (pin "2") (pinfunction "2_2") (pintype "passive"))
      (node (ref "U2") (pin "39") (pinfunction "RIGHT_39") (pintype "bidirectional"))
    )
    (net (code "36") (name "RST") (class "Default")
      (node (ref "J2") (pin "3") (pinfunction "3_3") (pintype "passive"))
      (node (ref "R6") (pin "1") (pinfunction "1_1") (pintype "passive"))
      (node (ref "U3") (pin "25") (pinfunction "PC6(/RESET)_25") (pintype "bidirectional"))
    )
    (net (code "37") (name "SCK") (class "Default")
      (node (ref "J2") (pin "5") (pinfunction "5_5") (pintype "passive"))
      (node (ref "R16") (pin "1") (pinfunction "1_1") (pintype "passive"))
      (node (ref "U3") (pin "15") (pinfunction "PB5(SCK)_15") (pintype "bidirectional"))
    )
    (net (code "38") (name "SCK*") (class "Default")
      (node (ref "R16") (pin "2") (pinfunction "2_2") (pintype "passive"))
      (node (ref "U2") (pin "28") (pinfunction "SCLK_28") (pintype "bidirectional"))
      (node (ref "X1") (pin "5") (pinfunction "CLK_5") (pintype "bidirectional"))
    )
    (net (code "39") (name "SS_SD") (class "Default")
      (node (ref "U3") (pin "12") (pinfunction "PB2(SS/OC1B)_12") (pintype "bidirectional"))
      (node (ref "X1") (pin "2") (pinfunction "CD/DAT3_2") (pintype "bidirectional"))
    )
    (net (code "40") (name "VCC") (class "Default")
      (node (ref "BSF1") (pin "VCC") (pinfunction "VCC_VCC") (pintype "bidirectional"))
      (node (ref "BSM1") (pin "VCC1") (pinfunction "VCC_VCC1") (pintype "bidirectional"))
      (node (ref "C14") (pin "2") (pinfunction "2_2") (pintype "passive"))
      (node (ref "C28") (pin "2") (pinfunction "2_2") (pintype "passive"))
      (node (ref "C30") (pin "1") (pinfunction "1_1") (pintype "passive"))
      (node (ref "C32") (pin "1") (pinfunction "1_1") (pintype "passive"))
      (node (ref "R8") (pin "1") (pinfunction "1_1") (pintype "passive"))
      (node (ref "U1") (pin "5") (pinfunction "V+_5") (pintype "power_in"))
      (node (ref "U4") (pin "1") (pinfunction "IN_1") (pintype "input"))
      (node (ref "U4") (pin "3") (pinfunction "EN_3") (pintype "input"))
      (node (ref "U5") (pin "1") (pinfunction "IN_1") (pintype "input"))
      (node (ref "U5") (pin "3") (pinfunction "EN_3") (pintype "input"))
      (node (ref "U6") (pin "5") (pinfunction "V+_5") (pintype "power_in"))
    )
    (net (code "41") (name "XCS") (class "Default")
      (node (ref "R17") (pin "1") (pinfunction "1_1") (pintype "passive"))
      (node (ref "U2") (pin "23") (pinfunction "XCS_23") (pintype "bidirectional"))
      (node (ref "U3") (pin "22") (pinfunction "PC3(ADC3)_22") (pintype "bidirectional"))
    )
    (net (code "42") (name "XDCS") (class "Default")
      (node (ref "U2") (pin "13") (pinfunction "XDCS/BSYNC_13") (pintype "bidirectional"))
      (node (ref "U3") (pin "20") (pinfunction "PC1(ADC1)_20") (pintype "bidirectional"))
    )
    (net (code "43") (name "XRST") (class "Default")
      (node (ref "R11") (pin "1") (pinfunction "1_1") (pintype "passive"))
      (node (ref "U2") (pin "3") (pinfunction "XRESET_3") (pintype "bidirectional"))
      (node (ref "U3") (pin "19") (pinfunction "PC0(ADC0)_19") (pintype "bidirectional"))
    )
    (net (code "44") (name "unconnected-(J1-Pad1)") (class "Default")
      (node (ref "J1") (pin "1") (pinfunction "1_1") (pintype "bidirectional"))
    )
    (net (code "45") (name "unconnected-(SW1-Pad4)") (class "Default")
      (node (ref "SW1") (pin "4") (pinfunction "4_4") (pintype "bidirectional"))
    )
    (net (code "46") (name "unconnected-(U2-LINE2-Pad48)") (class "Default")
      (node (ref "U2") (pin "48") (pinfunction "LINE2_48") (pintype "bidirectional"))
    )
    (net (code "47") (name "unconnected-(U2-MICN-Pad2)") (class "Default")
      (node (ref "U2") (pin "2") (pinfunction "MICN_2") (pintype "bidirectional"))
    )
    (net (code "48") (name "unconnected-(U2-MICP{slash}LINE1-Pad1)") (class "Default")
      (node (ref "U2") (pin "1") (pinfunction "MICP/LINE1_1") (pintype "bidirectional"))
    )
    (net (code "49") (name "unconnected-(U2-RX-Pad26)") (class "Default")
      (node (ref "U2") (pin "26") (pinfunction "RX_26") (pintype "bidirectional"))
    )
    (net (code "50") (name "unconnected-(U2-TX-Pad27)") (class "Default")
      (node (ref "U2") (pin "27") (pinfunction "TX_27") (pintype "bidirectional"))
    )
    (net (code "51") (name "unconnected-(U2-VCO-Pad15)") (class "Default")
      (node (ref "U2") (pin "15") (pinfunction "VCO_15") (pintype "bidirectional"))
    )
    (net (code "52") (name "unconnected-(U3-PB0(ICP)-Pad10)") (class "Default")
      (node (ref "U3") (pin "10") (pinfunction "PB0(ICP)_10") (pintype "bidirectional"))
    )
    (net (code "53") (name "unconnected-(U3-PB1(OC1A)-Pad11)") (class "Default")
      (node (ref "U3") (pin "11") (pinfunction "PB1(OC1A)_11") (pintype "bidirectional"))
    )
    (net (code "54") (name "unconnected-(U3-PB6(XTAL1{slash}TOSC1)-Pad5)") (class "Default")
      (node (ref "U3") (pin "5") (pinfunction "PB6(XTAL1/TOSC1)_5") (pintype "bidirectional"))
    )
    (net (code "55") (name "unconnected-(U3-PB7(XTAL2{slash}TOSC2)-Pad6)") (class "Default")
      (node (ref "U3") (pin "6") (pinfunction "PB7(XTAL2/TOSC2)_6") (pintype "bidirectional"))
    )
    (net (code "56") (name "unconnected-(U3-PC4(ADC4{slash}SDA)-Pad23)") (class "Default")
      (node (ref "U3") (pin "23") (pinfunction "PC4(ADC4/SDA)_23") (pintype "bidirectional"))
    )
    (net (code "57") (name "unconnected-(U3-PC5(ADC5{slash}SCL)-Pad24)") (class "Default")
      (node (ref "U3") (pin "24") (pinfunction "PC5(ADC5/SCL)_24") (pintype "bidirectional"))
    )
    (net (code "58") (name "unconnected-(U3-PD0(RXD)-Pad26)") (class "Default")
      (node (ref "U3") (pin "26") (pinfunction "PD0(RXD)_26") (pintype "bidirectional"))
    )
    (net (code "59") (name "unconnected-(U3-PD7(AIN1)-Pad9)") (class "Default")
      (node (ref "U3") (pin "9") (pinfunction "PD7(AIN1)_9") (pintype "bidirectional"))
    )
    (net (code "60") (name "unconnected-(X1-DAT1-Pad8)") (class "Default")
      (node (ref "X1") (pin "8") (pinfunction "DAT1_8") (pintype "bidirectional"))
    )
    (net (code "61") (name "unconnected-(X1-DAT2-Pad1)") (class "Default")
      (node (ref "X1") (pin "1") (pinfunction "DAT2_1") (pintype "bidirectional"))
    )
    (net (code "62") (name "unconnected-(X1-DET-Pad9)") (class "Default")
      (node (ref "X1") (pin "9") (pinfunction "DET_9") (pintype "bidirectional"))
    )
    (net (code "63") (name "unconnected-(X1-DET-Pad10)") (class "Default")
      (node (ref "X1") (pin "10") (pinfunction "DET_10") (pintype "bidirectional"))
    )
  )
)
